# SCH_555-Circuit_2025-10-19.net
KiCad netlist of a schematic drawn in EasyEDA
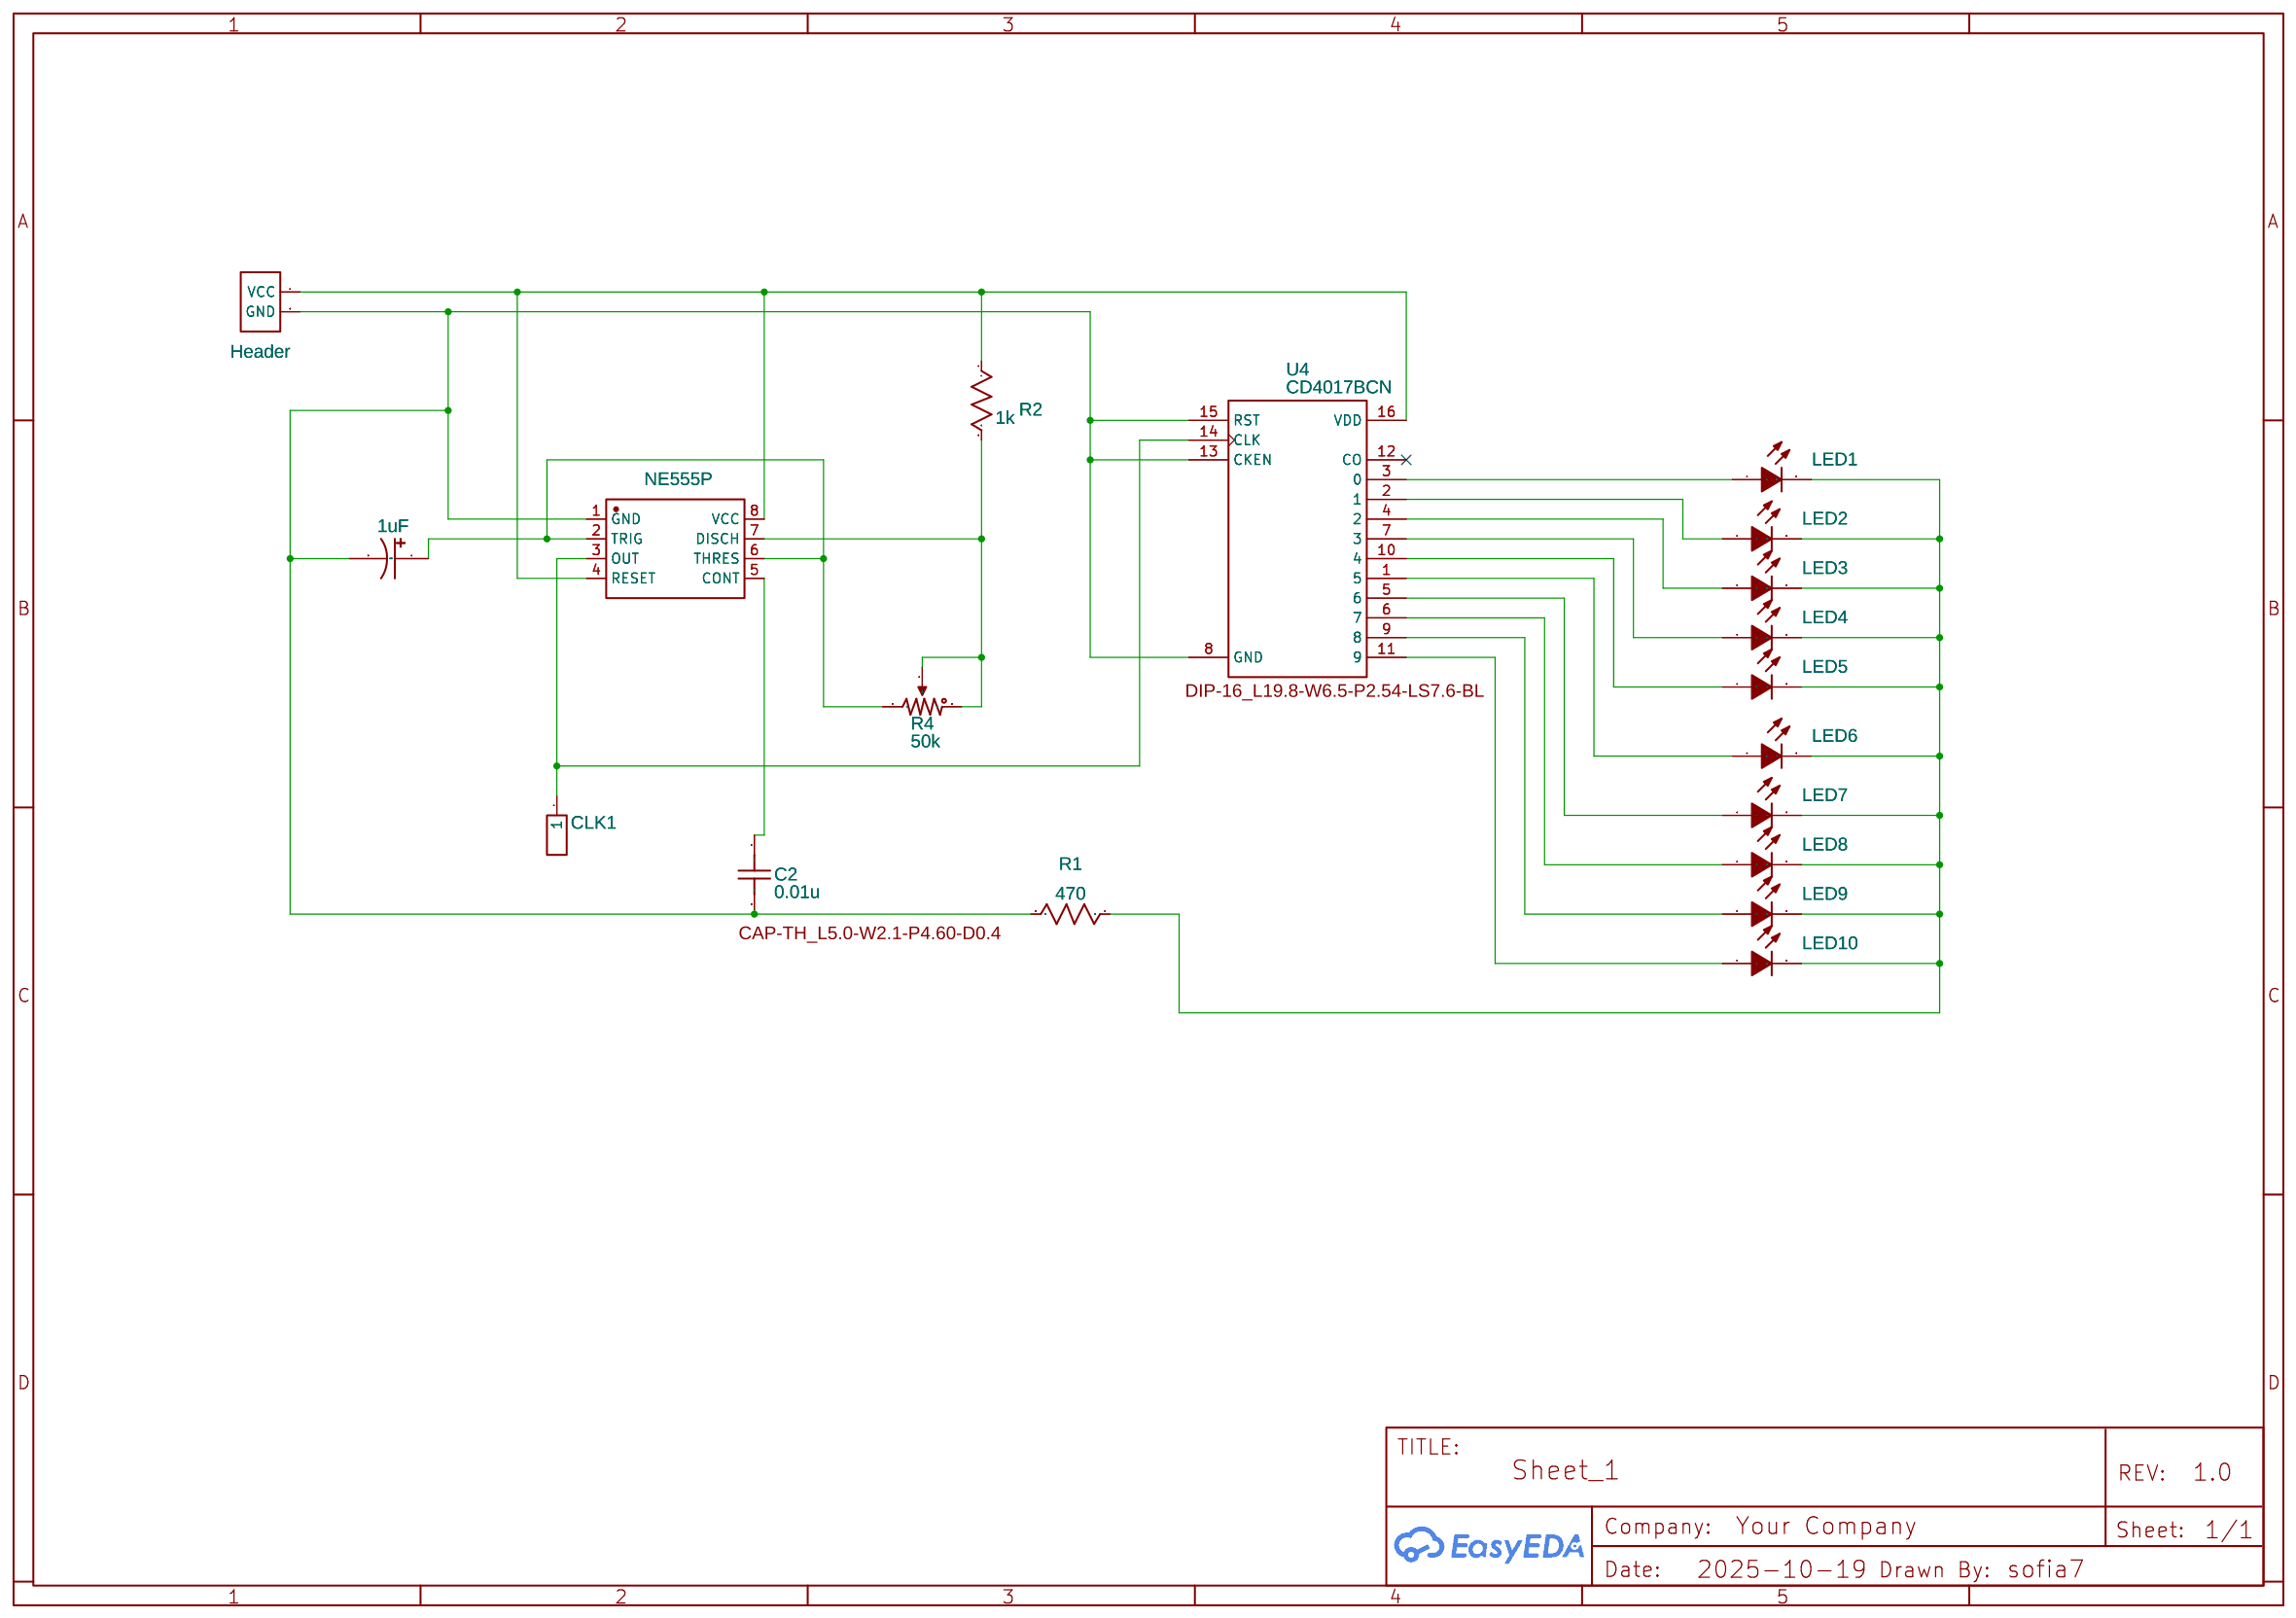
[diagram p0: schematic sheet]

(export (version "E")
  (design (tool "Eeschema 10.0.6"))
  (components
    (comp (ref "C1")
      (value "1uF")
      (fields (field (name "Manufacturer Part") "UVZ1H010MDD") (field (name "Manufacturer") "Nichicon(尼吉康)"))
      (libsource (lib "") (part "UVZ1H010MDD"))
    )
    (comp (ref "C2") (value "0.01u") (libsource (lib "") (part "C_0603_US")))
    (comp (ref "CLK1")
      (value "C81276")
      (fields
        (field (name "Manufacturer Part") "2.54-1*1P针")
        (field (name "Manufacturer") "BOOMELE(Boom Precision Elec)")
      )
      (libsource (lib "") (part "Header-Male-2.54_1x1"))
    )
    (comp (ref "H1") (value "Header") (libsource (lib "") (part "HEADER-FEMALE-2.54_1X2")))
    (comp (ref "LED1") (value "LED_5MM") (libsource (lib "") (part "LED_5MM")))
    (comp (ref "LED2") (value "LED_5MM") (libsource (lib "") (part "LED_5MM")))
    (comp (ref "LED3") (value "LED_5MM") (libsource (lib "") (part "LED_5MM")))
    (comp (ref "LED4") (value "LED_5MM") (libsource (lib "") (part "LED_5MM")))
    (comp (ref "LED5") (value "LED_5MM") (libsource (lib "") (part "LED_5MM")))
    (comp (ref "LED6") (value "LED_5MM") (libsource (lib "") (part "LED_5MM")))
    (comp (ref "LED7") (value "LED_5MM") (libsource (lib "") (part "LED_5MM")))
    (comp (ref "LED8") (value "LED_5MM") (libsource (lib "") (part "LED_5MM")))
    (comp (ref "LED9") (value "LED_5MM") (libsource (lib "") (part "LED_5MM")))
    (comp (ref "LED10") (value "LED_5MM") (libsource (lib "") (part "LED_5MM")))
    (comp (ref "R1")
      (value "470")
      (fields (field (name "Manufacturer Part") "?"))
      (libsource (lib "") (part "Resistor_1"))
    )
    (comp (ref "R2")
      (value "1k")
      (fields (field (name "Manufacturer Part") "?"))
      (libsource (lib "") (part "Resistor"))
    )
    (comp (ref "R4")
      (value "50k")
      (fields (field (name "Manufacturer Part") "?"))
      (libsource (lib "") (part "Potentiometer"))
    )
    (comp (ref "U2")
      (value "NE555P")
      (fields (field (name "Manufacturer") "TI(德州仪器)"))
      (libsource (lib "") (part "NE555P"))
    )
    (comp (ref "U4") (value "CD4017BCN") (libsource (lib "") (part "CD4017BCN")))
  )
  (nets
    (net (code "1") (name "Net-(H1-GND)") (class "Default")
      (node (ref "C1") (pin "2") (pinfunction "2_2") (pintype "unspecified"))
      (node (ref "C2") (pin "2") (pinfunction "2_2") (pintype "unspecified"))
      (node (ref "H1") (pin "2") (pinfunction "GND_2") (pintype "unspecified"))
      (node (ref "R1") (pin "2") (pinfunction "2_2") (pintype "unspecified"))
      (node (ref "U2") (pin "1") (pinfunction "GND_1") (pintype "unspecified"))
      (node (ref "U4") (pin "13") (pinfunction "CKEN_13") (pintype "unspecified"))
      (node (ref "U4") (pin "15") (pinfunction "RST_15") (pintype "unspecified"))
      (node (ref "U4") (pin "8") (pinfunction "GND_8") (pintype "passive"))
    )
    (net (code "2") (name "Net-(H1-VCC)") (class "Default")
      (node (ref "H1") (pin "1") (pinfunction "VCC_1") (pintype "unspecified"))
      (node (ref "R2") (pin "1") (pinfunction "1_1") (pintype "unspecified"))
      (node (ref "U2") (pin "4") (pinfunction "RESET_4") (pintype "unspecified"))
      (node (ref "U2") (pin "8") (pinfunction "VCC_8") (pintype "unspecified"))
      (node (ref "U4") (pin "16") (pinfunction "VDD_16") (pintype "passive"))
    )
    (net (code "3") (name "Net-(LED1-A)") (class "Default")
      (node (ref "LED1") (pin "1") (pinfunction "A_1") (pintype "input"))
      (node (ref "U4") (pin "3") (pinfunction "0_3") (pintype "output"))
    )
    (net (code "4") (name "Net-(LED1-K)") (class "Default")
      (node (ref "LED1") (pin "2") (pinfunction "K_2") (pintype "input"))
      (node (ref "LED10") (pin "2") (pinfunction "K_2") (pintype "input"))
      (node (ref "LED2") (pin "2") (pinfunction "K_2") (pintype "input"))
      (node (ref "LED3") (pin "2") (pinfunction "K_2") (pintype "input"))
      (node (ref "LED4") (pin "2") (pinfunction "K_2") (pintype "input"))
      (node (ref "LED5") (pin "2") (pinfunction "K_2") (pintype "input"))
      (node (ref "LED6") (pin "2") (pinfunction "K_2") (pintype "input"))
      (node (ref "LED7") (pin "2") (pinfunction "K_2") (pintype "input"))
      (node (ref "LED8") (pin "2") (pinfunction "K_2") (pintype "input"))
      (node (ref "LED9") (pin "2") (pinfunction "K_2") (pintype "input"))
      (node (ref "R1") (pin "1") (pinfunction "1_1") (pintype "unspecified"))
    )
    (net (code "5") (name "Net-(LED2-A)") (class "Default")
      (node (ref "LED2") (pin "1") (pinfunction "A_1") (pintype "input"))
      (node (ref "U4") (pin "2") (pinfunction "1_2") (pintype "output"))
    )
    (net (code "6") (name "Net-(LED3-A)") (class "Default")
      (node (ref "LED3") (pin "1") (pinfunction "A_1") (pintype "input"))
      (node (ref "U4") (pin "4") (pinfunction "2_4") (pintype "output"))
    )
    (net (code "7") (name "Net-(LED4-A)") (class "Default")
      (node (ref "LED4") (pin "1") (pinfunction "A_1") (pintype "input"))
      (node (ref "U4") (pin "7") (pinfunction "3_7") (pintype "output"))
    )
    (net (code "8") (name "Net-(LED5-A)") (class "Default")
      (node (ref "LED5") (pin "1") (pinfunction "A_1") (pintype "input"))
      (node (ref "U4") (pin "10") (pinfunction "4_10") (pintype "output"))
    )
    (net (code "9") (name "Net-(LED6-A)") (class "Default")
      (node (ref "LED6") (pin "1") (pinfunction "A_1") (pintype "input"))
      (node (ref "U4") (pin "1") (pinfunction "5_1") (pintype "output"))
    )
    (net (code "10") (name "Net-(LED7-A)") (class "Default")
      (node (ref "LED7") (pin "1") (pinfunction "A_1") (pintype "input"))
      (node (ref "U4") (pin "5") (pinfunction "6_5") (pintype "output"))
    )
    (net (code "11") (name "Net-(LED8-A)") (class "Default")
      (node (ref "LED8") (pin "1") (pinfunction "A_1") (pintype "input"))
      (node (ref "U4") (pin "6") (pinfunction "7_6") (pintype "output"))
    )
    (net (code "12") (name "Net-(LED9-A)") (class "Default")
      (node (ref "LED9") (pin "1") (pinfunction "A_1") (pintype "input"))
      (node (ref "U4") (pin "9") (pinfunction "8_9") (pintype "output"))
    )
    (net (code "13") (name "Net-(LED10-A)") (class "Default")
      (node (ref "LED10") (pin "1") (pinfunction "A_1") (pintype "input"))
      (node (ref "U4") (pin "11") (pinfunction "9_11") (pintype "output"))
    )
    (net (code "14") (name "Net-(R4-2)") (class "Default")
      (node (ref "R2") (pin "2") (pinfunction "2_2") (pintype "unspecified"))
      (node (ref "R4") (pin "2") (pinfunction "3_2") (pintype "unspecified"))
      (node (ref "R4") (pin "3") (pinfunction "2_3") (pintype "unspecified"))
      (node (ref "U2") (pin "7") (pinfunction "DISCH_7") (pintype "unspecified"))
    )
    (net (code "15") (name "Net-(U2-CONT)") (class "Default")
      (node (ref "C2") (pin "1") (pinfunction "1_1") (pintype "unspecified"))
      (node (ref "U2") (pin "5") (pinfunction "CONT_5") (pintype "unspecified"))
    )
    (net (code "16") (name "Net-(U2-OUT)") (class "Default")
      (node (ref "CLK1") (pin "1") (pinfunction "1_1") (pintype "unspecified"))
      (node (ref "U2") (pin "3") (pinfunction "OUT_3") (pintype "unspecified"))
      (node (ref "U4") (pin "14") (pinfunction "CLK_14") (pintype "unspecified"))
    )
    (net (code "17") (name "Net-(U2-THRES)") (class "Default")
      (node (ref "C1") (pin "1") (pinfunction "1_1") (pintype "unspecified"))
      (node (ref "R4") (pin "1") (pinfunction "1_1") (pintype "unspecified"))
      (node (ref "U2") (pin "2") (pinfunction "TRIG_2") (pintype "unspecified"))
      (node (ref "U2") (pin "6") (pinfunction "THRES_6") (pintype "unspecified"))
    )
    (net (code "18") (name "unconnected-(U4-CO-Pad12)") (class "Default")
      (node (ref "U4") (pin "12") (pinfunction "CO_12") (pintype "output+no_connect"))
    )
  )
)
